# Boom_Deployment.net
KiCad netlist of a schematic drawn in Altium Designer
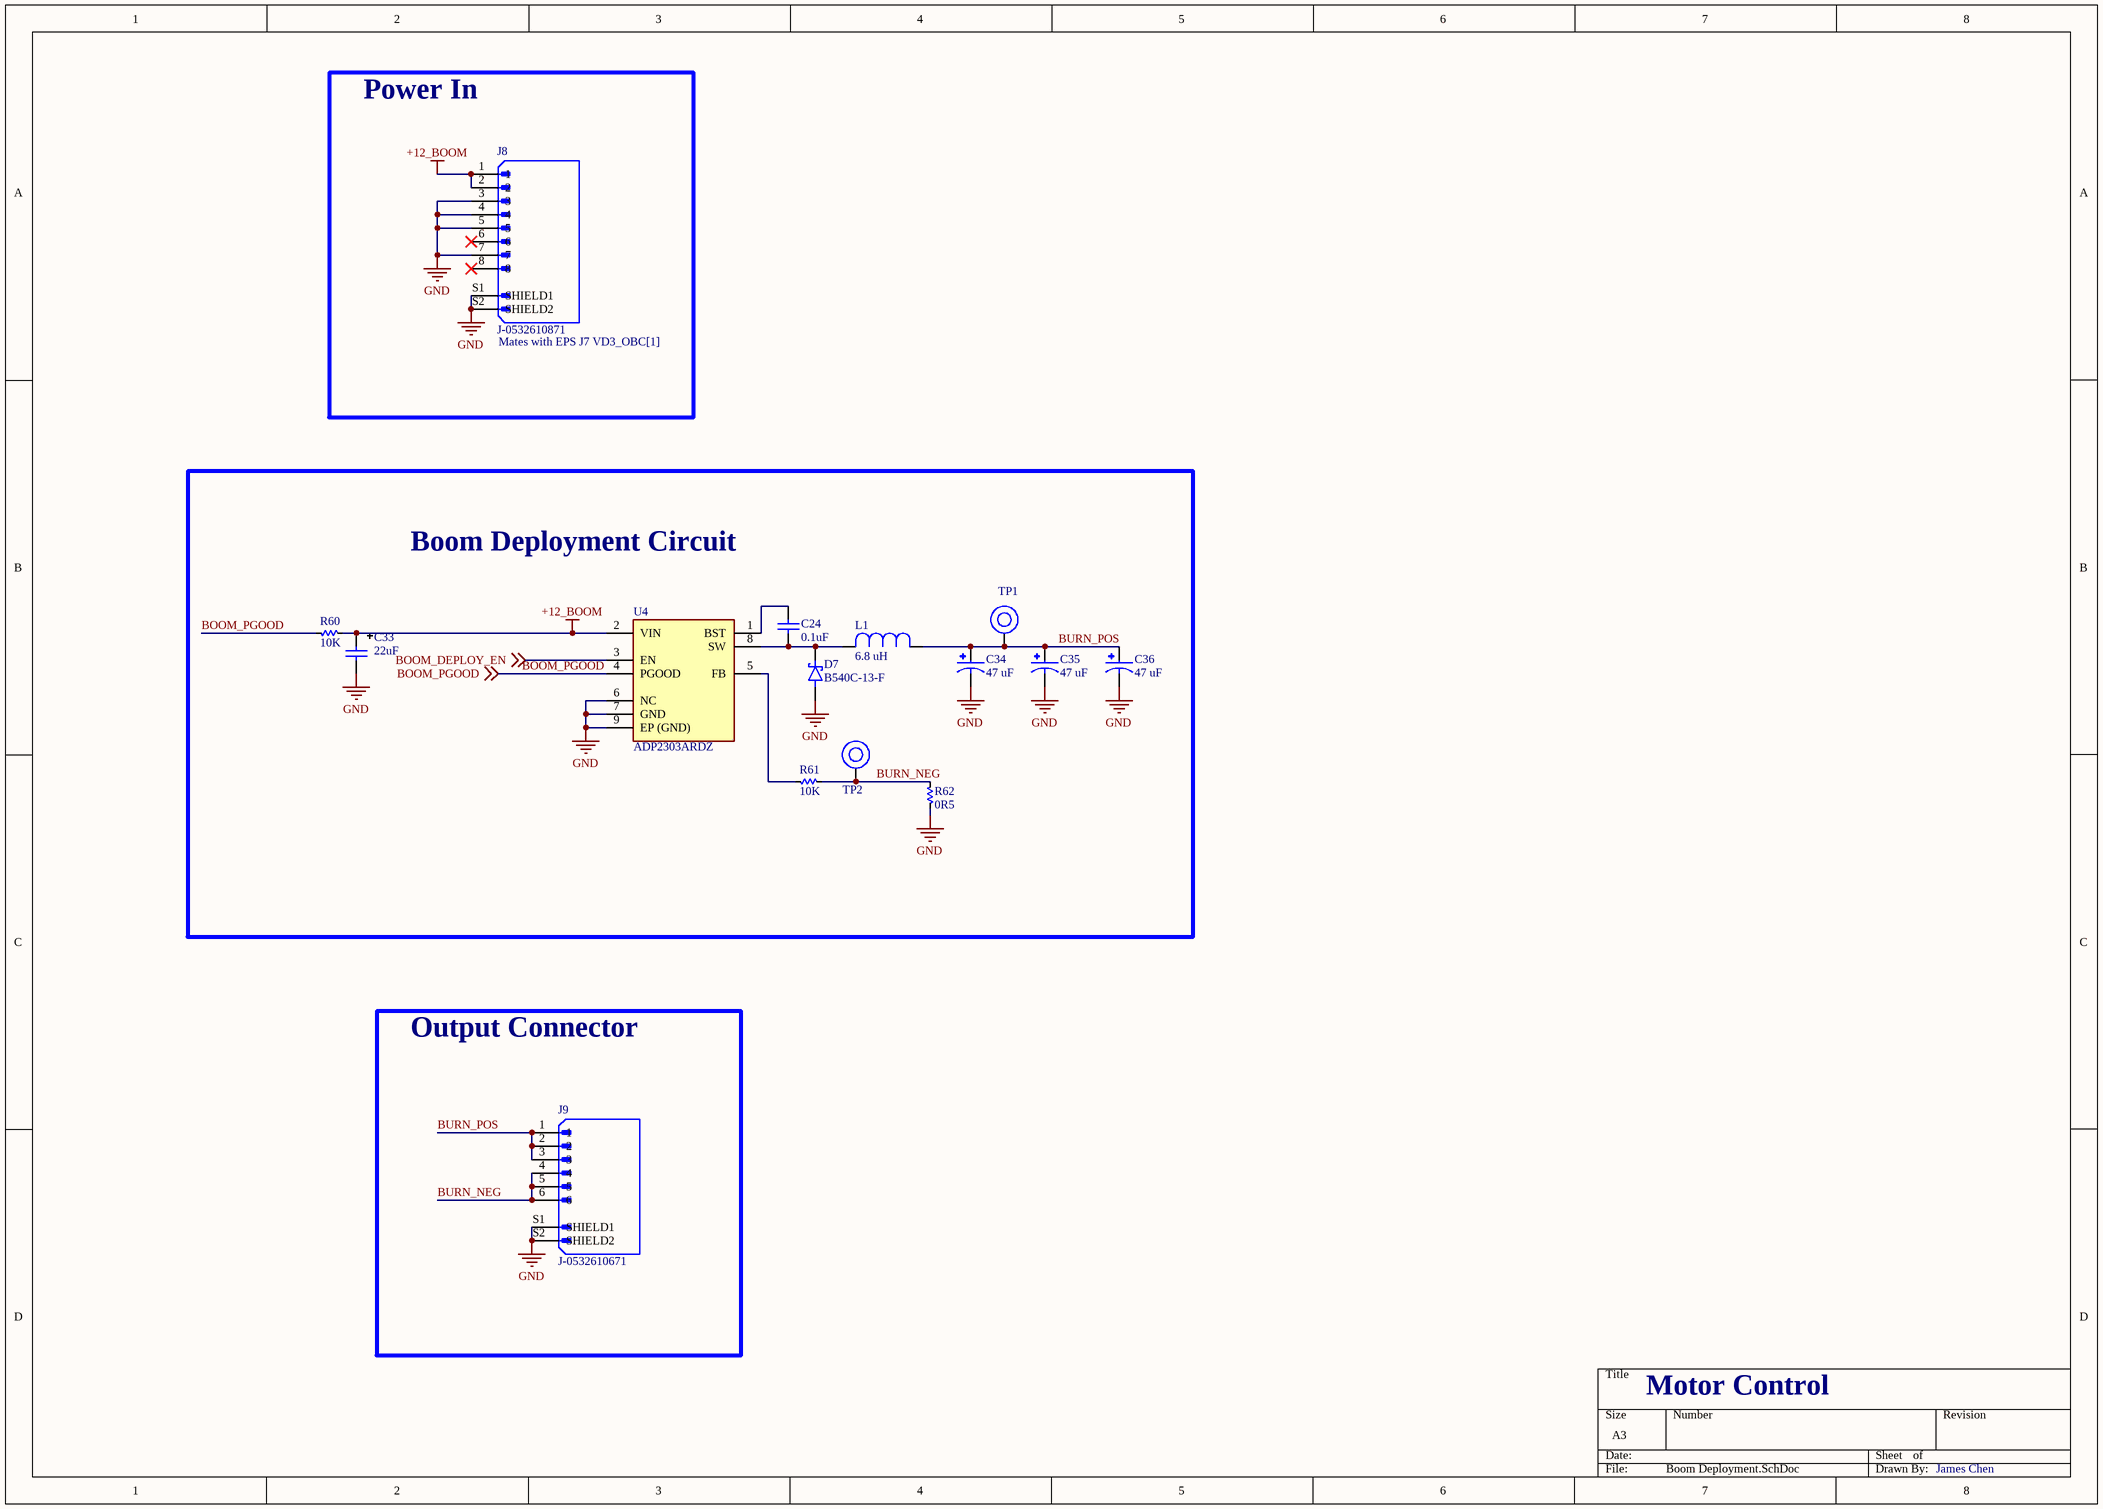
[diagram p0: Boom Deployment.SchDoc]

(export (version "E")
  (design (tool "Eeschema 10.0.6"))
  (components
    (comp (ref "C24")
      (value "0.1uF")
      (footprint "0603")
      (description "0.1 µF ±10% 25V Ceramic Capacitor X7R 0603 (1608 Metric)")
      (fields
        (field (name "DISTRIBUTOR PART #") "1276-1006-1-ND")
        (field (name "MANUFACTURER") "Samsung Electro-Mechanics")
      )
      (libsource (lib "Burn Wire Dev Board") (part "CC-104-K-25V-X7R-0603"))
    )
    (comp (ref "C33")
      (value "22uF")
      (footprint "CAP TANT 1206 (A) TCJ")
      (description "CAP TANT 22UF 10% 10V 1206")
      (fields
        (field (name "DISTRIBUTOR PART #") "478-11193-1-ND")
        (field (name "MANUFACTURER") "KYOCERA AVX")
      )
      (libsource (lib "Burn Wire Dev Board") (part "CT-225-M-20V-OTH-1206"))
    )
    (comp (ref "C34")
      (value "47 uF")
      (footprint "CC-25SVPF47M")
      (description "CAP ALUM POLY 47UF 20% 25V SMD")
      (fields
        (field (name "DISTRIBUTOR PART #") "P16513CT-ND")
        (field (name "MANUFACTURER") "Panasonic Electronic Components")
      )
      (libsource (lib "Burn Wire Dev Board") (part "CC-25SVPF47M"))
    )
    (comp (ref "C35")
      (value "47 uF")
      (footprint "CC-25SVPF47M")
      (description "CAP ALUM POLY 47UF 20% 25V SMD")
      (fields
        (field (name "DISTRIBUTOR PART #") "P16513CT-ND")
        (field (name "MANUFACTURER") "Panasonic Electronic Components")
      )
      (libsource (lib "Burn Wire Dev Board") (part "CC-25SVPF47M"))
    )
    (comp (ref "C36")
      (value "47 uF")
      (footprint "CC-25SVPF47M")
      (description "CAP ALUM POLY 47UF 20% 25V SMD")
      (fields
        (field (name "DISTRIBUTOR PART #") "P16513CT-ND")
        (field (name "MANUFACTURER") "Panasonic Electronic Components")
      )
      (libsource (lib "Burn Wire Dev Board") (part "CC-25SVPF47M"))
    )
    (comp (ref "D7")
      (value "B540C-13-F")
      (footprint "D-B540C-13-F")
      (description "DIODE SCHOTTKY 40V 5A SMC")
      (fields
        (field (name "MANUFACTURER") "Diodes Incorporated")
        (field (name "DISTRIBUTOR PART #") "B540C-FDICT-ND")
      )
      (libsource (lib "Burn Wire Dev Board") (part "D-B540C-13-F"))
    )
    (comp (ref "J8")
      (value "J-0532610871")
      (footprint "J-532610871")
      (description "CONN HEADER SMD R/A 8POS 1.25MM")
      (fields
        (field (name "MANFACTURER PART #") "0532610871")
        (field (name "DISTRIBUTOR PART #") "WM7626CT-ND")
      )
      (libsource (lib "OBC Development Board") (part "J-0532610871"))
    )
    (comp (ref "J9")
      (value "J-0532610671")
      (footprint "J-0532610671")
      (description "CONN HEADER SMD R/A 6POS 1.25MM")
      (fields
        (field (name "MANFACTURER PART #") "0532610671")
        (field (name "DISTRIBUTOR PART #") "WM7624CT-ND")
      )
      (libsource (lib "Burn Wire Dev Board") (part "J-0532610671"))
    )
    (comp (ref "L1")
      (value "6.8 uH")
      (footprint "L-IHLP4040DZER6R8M01")
      (description "FIXED IND 6.8UH 8A 23.3 MOHM SMD")
      (fields
        (field (name "MANUFACTURER") "Vishay Dale")
        (field (name "MANUFACTURER PART #") "IHLP4040DZER6R8M01")
      )
      (libsource (lib "Burn Wire Dev Board") (part "L-IHLP4040DZER6R8M01"))
    )
    (comp (ref "R60")
      (value "10K")
      (footprint "0603")
      (description "RES 10K OHM 1% 1/8W 0603")
      (fields
        (field (name "DISTRIBUTOR PART #") "RNCP0603FTD10K0CT-ND")
        (field (name "MANUFACTURER") "Stackpole Electronics Inc")
      )
      (libsource (lib "Burn Wire Dev Board") (part "RT-10K0-F-1/16W-0603"))
    )
    (comp (ref "R61")
      (value "10K")
      (footprint "0603")
      (description "RES 10K OHM 1% 1/8W 0603")
      (fields
        (field (name "DISTRIBUTOR PART #") "RNCP0603FTD10K0CT-ND")
        (field (name "MANUFACTURER") "Stackpole Electronics Inc")
      )
      (libsource (lib "Burn Wire Dev Board") (part "RT-10K0-F-1/16W-0603"))
    )
    (comp (ref "R62")
      (value "0R5")
      (footprint "4527")
      (description "2W ±75ppm/℃ ±1% 250mΩ 4527 Chip Resistor - Surface Mount ROHS")
      (fields (field (name "DISTRIBUTOR PART #") "C4299447") (field (name "MANUFACTURER") "Vishay Dale"))
      (libsource (lib "OBC Development Board") (part "RT-0R5-F-2W-4527"))
    )
    (comp (ref "TP1")
      (value "TP")
      (footprint "TP")
      (description "Test Point")
      (libsource (lib "PowerManagmentBoard_V4.0") (part "TP"))
    )
    (comp (ref "TP2")
      (value "TP")
      (footprint "TP")
      (description "Test Point")
      (libsource (lib "PowerManagmentBoard_V4.0") (part "TP"))
    )
    (comp (ref "U4")
      (value "ADP2303ARDZ")
      (footprint "U-ADP2303ARDZ")
      (description "IC REG BUCK ADJUSTABLE 3A 8SOIC")
      (fields
        (field (name "MANUFACTURER") "Analog Devices Inc.")
        (field (name "DISTRIBUTOR PART #") "505-ADP2303ARDZ-ND")
      )
      (libsource (lib "Burn Wire Dev Board") (part "U-ADP2303ARDZ"))
    )
  )
  (nets
    (net (code "1") (name "+12_BOOM") (class "Default")
      (node (ref "C33") (pin "1") (pinfunction "1_1") (pintype "passive"))
      (node (ref "J8") (pin "1") (pinfunction "1_1") (pintype "passive"))
      (node (ref "J8") (pin "2") (pinfunction "2_2") (pintype "passive"))
      (node (ref "R60") (pin "2") (pintype "passive"))
      (node (ref "U4") (pin "2") (pinfunction "VIN_2") (pintype "passive"))
    )
    (net (code "3") (name "/BURN_NEG") (class "Default")
      (node (ref "J9") (pin "4") (pinfunction "4_4") (pintype "passive"))
      (node (ref "J9") (pin "5") (pinfunction "5_5") (pintype "passive"))
      (node (ref "J9") (pin "6") (pinfunction "6_6") (pintype "passive"))
      (node (ref "R61") (pin "2") (pintype "passive"))
      (node (ref "R62") (pin "2") (pintype "passive"))
      (node (ref "TP2") (pin "1") (pinfunction "1_1") (pintype "passive"))
    )
    (net (code "4") (name "/BURN_POS") (class "Default")
      (node (ref "C34") (pin "1") (pinfunction "1_1") (pintype "passive"))
      (node (ref "C35") (pin "1") (pinfunction "1_1") (pintype "passive"))
      (node (ref "C36") (pin "1") (pinfunction "1_1") (pintype "passive"))
      (node (ref "J9") (pin "1") (pinfunction "1_1") (pintype "passive"))
      (node (ref "J9") (pin "2") (pinfunction "2_2") (pintype "passive"))
      (node (ref "J9") (pin "3") (pinfunction "3_3") (pintype "passive"))
      (node (ref "L1") (pin "1") (pinfunction "1_1") (pintype "passive"))
      (node (ref "TP1") (pin "1") (pinfunction "1_1") (pintype "passive"))
    )
    (net (code "5") (name "BOOM_DEPLOY_EN") (class "Default")
      (node (ref "U4") (pin "3") (pinfunction "EN_3") (pintype "passive"))
    )
    (net (code "6") (name "BOOM_PGOOD") (class "Default")
      (node (ref "R60") (pin "1") (pintype "passive"))
      (node (ref "U4") (pin "4") (pinfunction "PGOOD_4") (pintype "passive"))
    )
    (net (code "7") (name "GND") (class "Default")
      (node (ref "C33") (pin "2") (pinfunction "2_2") (pintype "passive"))
      (node (ref "C34") (pin "2") (pinfunction "2_2") (pintype "passive"))
      (node (ref "C35") (pin "2") (pinfunction "2_2") (pintype "passive"))
      (node (ref "C36") (pin "2") (pinfunction "2_2") (pintype "passive"))
      (node (ref "D7") (pin "A") (pinfunction "A_A") (pintype "passive"))
      (node (ref "J8") (pin "3") (pinfunction "3_3") (pintype "passive"))
      (node (ref "J8") (pin "4") (pinfunction "4_4") (pintype "passive"))
      (node (ref "J8") (pin "5") (pinfunction "5_5") (pintype "passive"))
      (node (ref "J8") (pin "7") (pinfunction "7_7") (pintype "passive"))
      (node (ref "J8") (pin "S1") (pinfunction "SHIELD1_S1") (pintype "passive"))
      (node (ref "J8") (pin "S2") (pinfunction "SHIELD2_S2") (pintype "passive"))
      (node (ref "J9") (pin "S1") (pinfunction "SHIELD1_S1") (pintype "passive"))
      (node (ref "J9") (pin "S2") (pinfunction "SHIELD2_S2") (pintype "passive"))
      (node (ref "R62") (pin "1") (pintype "passive"))
      (node (ref "U4") (pin "6") (pinfunction "NC_6") (pintype "passive"))
      (node (ref "U4") (pin "7") (pinfunction "GND_7") (pintype "passive"))
      (node (ref "U4") (pin "9") (pinfunction "EP_(GND)_9") (pintype "passive"))
    )
    (net (code "8") (name "Net-(D7-K)") (class "Default")
      (node (ref "C24") (pin "1") (pinfunction "1_1") (pintype "passive"))
      (node (ref "D7") (pin "C") (pinfunction "K_C") (pintype "passive"))
      (node (ref "L1") (pin "2") (pinfunction "2_2") (pintype "passive"))
      (node (ref "U4") (pin "8") (pinfunction "SW_8") (pintype "passive"))
    )
    (net (code "9") (name "Net-(U4-BST)") (class "Default")
      (node (ref "C24") (pin "2") (pinfunction "2_2") (pintype "passive"))
      (node (ref "U4") (pin "1") (pinfunction "BST_1") (pintype "passive"))
    )
    (net (code "10") (name "Net-(U4-FB)") (class "Default")
      (node (ref "R61") (pin "1") (pintype "passive"))
      (node (ref "U4") (pin "5") (pinfunction "FB_5") (pintype "passive"))
    )
    (net (code "11") (name "unconnected-(J8-Pad6)") (class "Default")
      (node (ref "J8") (pin "6") (pinfunction "6_6") (pintype "passive+no_connect"))
    )
    (net (code "12") (name "unconnected-(J8-Pad8)") (class "Default")
      (node (ref "J8") (pin "8") (pinfunction "8_8") (pintype "passive+no_connect"))
    )
  )
)
